# DESIGN7ES.net
KiCad netlist of a schematic drawn in EAGLE
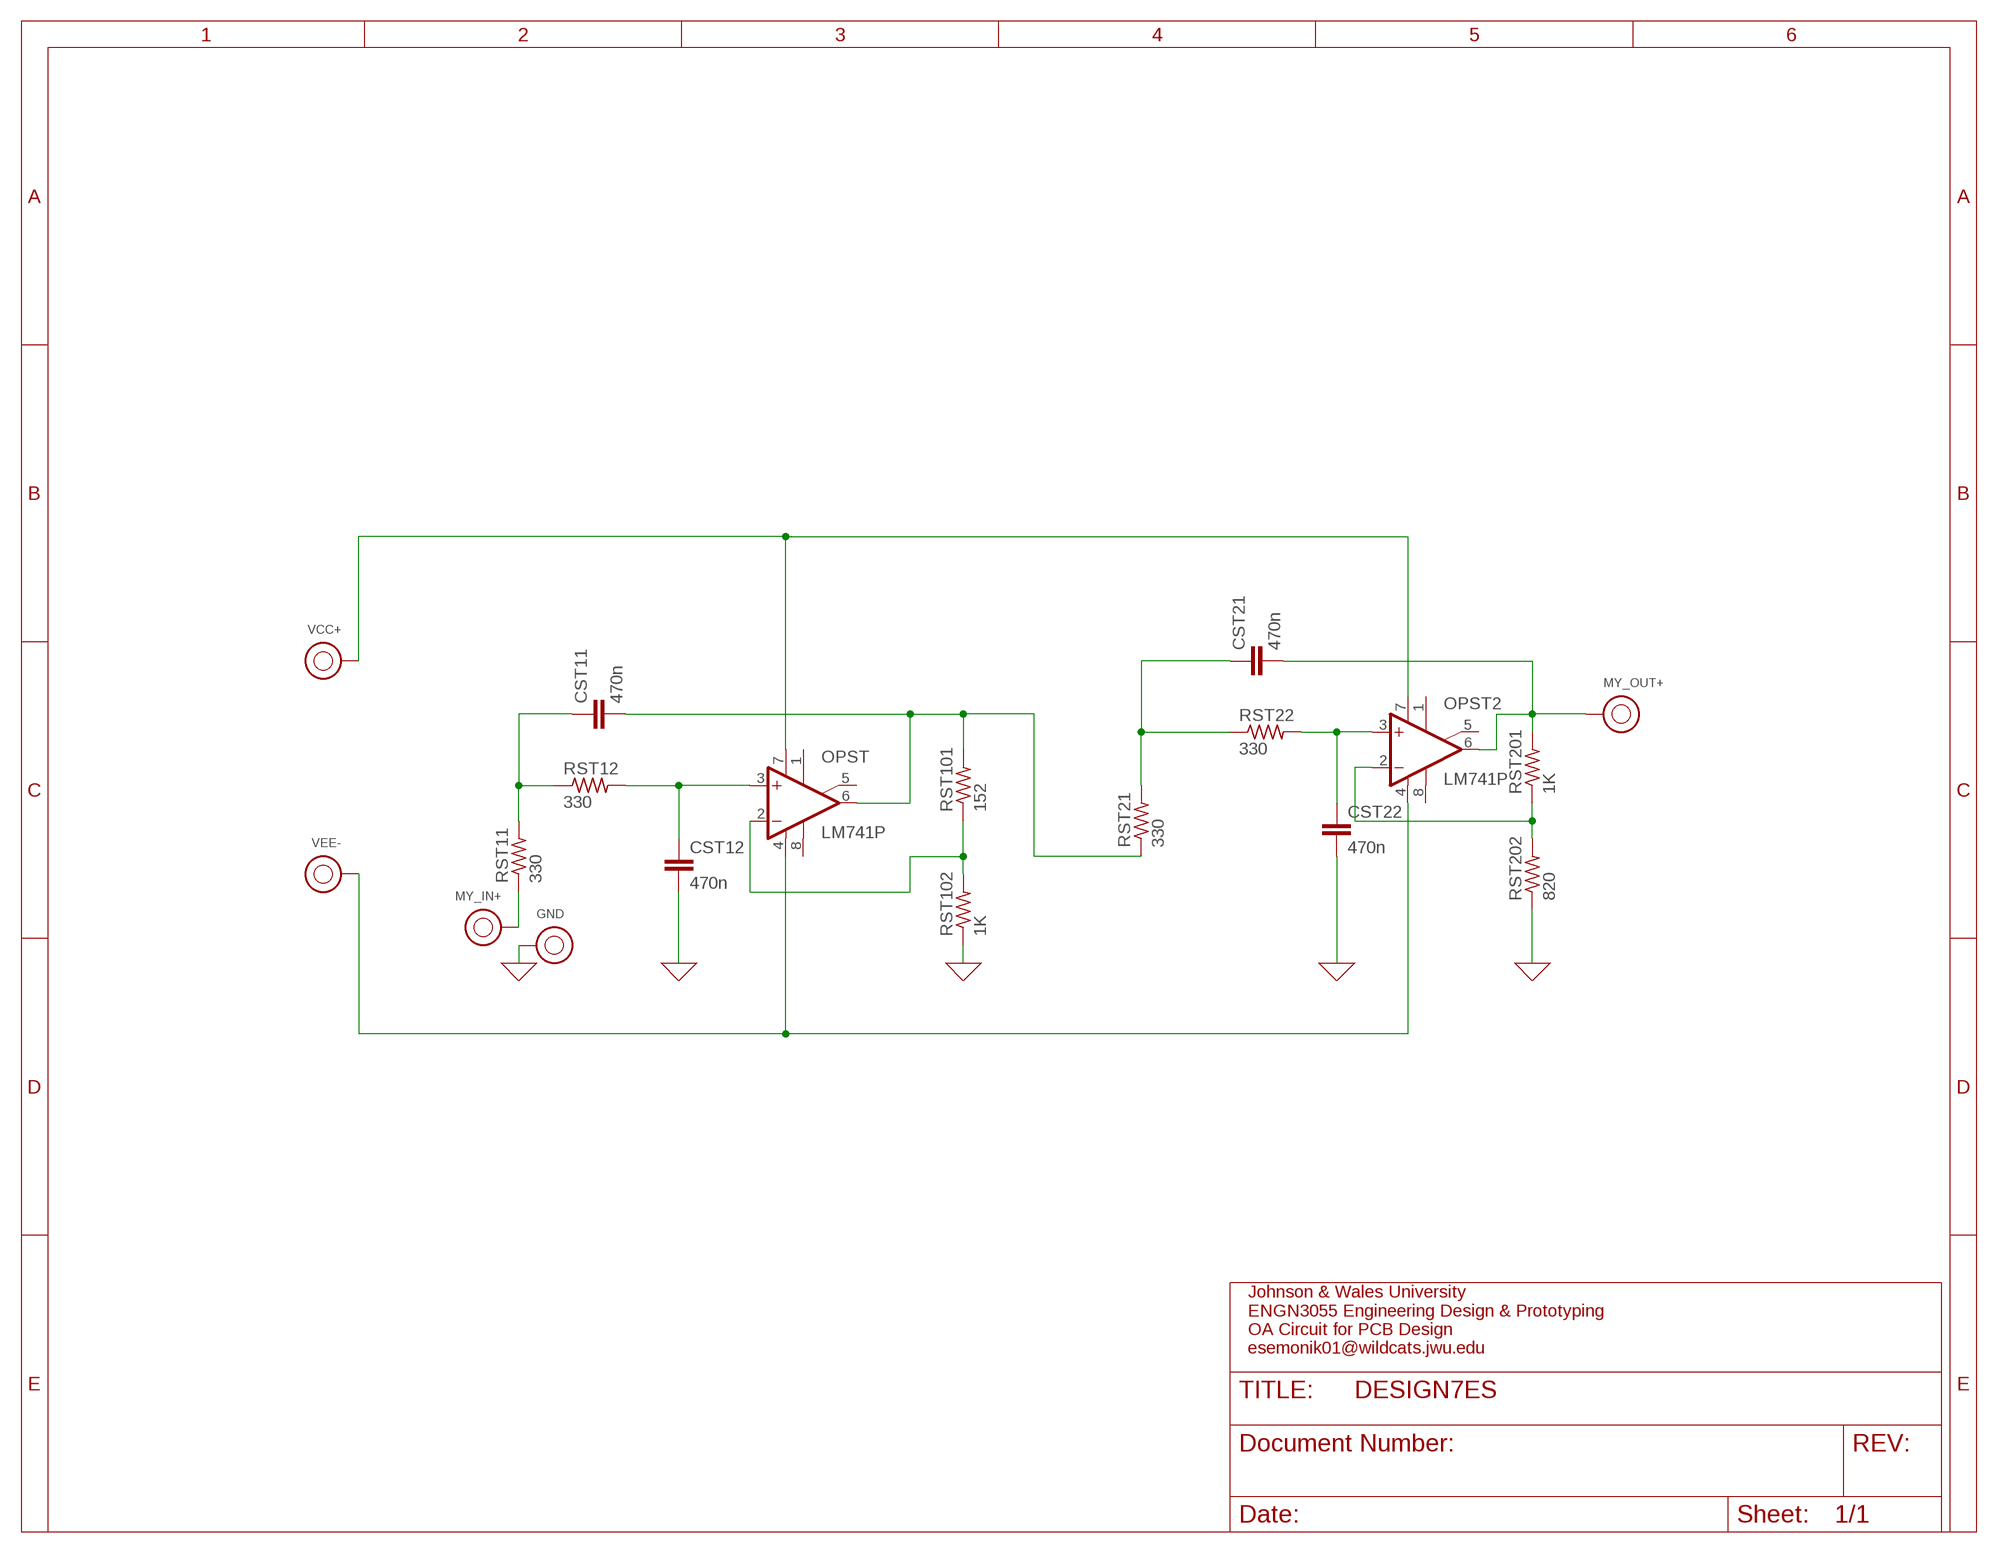
[diagram p0: schematic, sheet 1]

(export (version "E")
  (design (tool "Eeschema 10.0.6"))
  (components
    (comp (ref "CST11")
      (value "470n")
      (footprint "eagle-import:C2.5-2")
      (libsource (lib "eagle-import") (part "C2.5/2"))
    )
    (comp (ref "CST12")
      (value "470n")
      (footprint "eagle-import:C2.5-2")
      (libsource (lib "eagle-import") (part "C2.5/2"))
    )
    (comp (ref "CST21")
      (value "470n")
      (footprint "eagle-import:C2.5-2")
      (libsource (lib "eagle-import") (part "C2.5/2"))
    )
    (comp (ref "CST22")
      (value "470n")
      (footprint "eagle-import:C2.5-2")
      (libsource (lib "eagle-import") (part "C2.5/2"))
    )
    (comp (ref "GND")
      (value "BINDING-POST")
      (footprint "eagle-import:BINDING-POST")
      (libsource (lib "eagle-import") (part "BINDING-POST"))
    )
    (comp (ref "MY_IN+")
      (value "BINDING-POST")
      (footprint "eagle-import:BINDING-POST")
      (libsource (lib "eagle-import") (part "BINDING-POST"))
    )
    (comp (ref "MY_OUT+")
      (value "BINDING-POST")
      (footprint "eagle-import:BINDING-POST")
      (libsource (lib "eagle-import") (part "BINDING-POST"))
    )
    (comp (ref "OPST")
      (value "LM741P")
      (footprint "eagle-import:DIL08")
      (libsource (lib "eagle-import") (part "741PLM"))
    )
    (comp (ref "OPST2")
      (value "LM741P")
      (footprint "eagle-import:DIL08")
      (libsource (lib "eagle-import") (part "741PLM"))
    )
    (comp (ref "RST11")
      (value "330")
      (footprint "eagle-import:0204_5")
      (libsource (lib "eagle-import") (part "R-US_0204/5"))
    )
    (comp (ref "RST12")
      (value "330")
      (footprint "eagle-import:0204_5")
      (libsource (lib "eagle-import") (part "R-US_0204/5"))
    )
    (comp (ref "RST21")
      (value "330")
      (footprint "eagle-import:0204_5")
      (libsource (lib "eagle-import") (part "R-US_0204/5"))
    )
    (comp (ref "RST22")
      (value "330")
      (footprint "eagle-import:0204_5")
      (libsource (lib "eagle-import") (part "R-US_0204/5"))
    )
    (comp (ref "RST101")
      (value "152")
      (footprint "eagle-import:0204_5")
      (libsource (lib "eagle-import") (part "R-US_0204/5"))
    )
    (comp (ref "RST102")
      (value "1K")
      (footprint "eagle-import:0204_5")
      (libsource (lib "eagle-import") (part "R-US_0204/5"))
    )
    (comp (ref "RST201")
      (value "1K")
      (footprint "eagle-import:0204_5")
      (libsource (lib "eagle-import") (part "R-US_0204/5"))
    )
    (comp (ref "RST202")
      (value "820")
      (footprint "eagle-import:0204_5")
      (libsource (lib "eagle-import") (part "R-US_0204/5"))
    )
    (comp (ref "VCC+")
      (value "BINDING-POST")
      (footprint "eagle-import:BINDING-POST")
      (libsource (lib "eagle-import") (part "BINDING-POST"))
    )
    (comp (ref "VEE-")
      (value "BINDING-POST")
      (footprint "eagle-import:BINDING-POST")
      (libsource (lib "eagle-import") (part "BINDING-POST"))
    )
  )
  (nets
    (net (code "1") (name "GND") (class "Default")
      (node (ref "CST12") (pin "2") (pinfunction "2_2") (pintype "passive"))
      (node (ref "CST22") (pin "2") (pinfunction "2_2") (pintype "passive"))
      (node (ref "GND") (pin "1") (pinfunction "1_1") (pintype "passive"))
      (node (ref "GND") (pin "1_1") (pinfunction "1_1_1") (pintype "passive"))
      (node (ref "GND") (pin "1_2") (pinfunction "1_1_2") (pintype "passive"))
      (node (ref "GND") (pin "1_3") (pinfunction "1_1_3") (pintype "passive"))
      (node (ref "GND") (pin "1_4") (pinfunction "1_1_4") (pintype "passive"))
      (node (ref "GND") (pin "1_5") (pinfunction "1_1_5") (pintype "passive"))
      (node (ref "GND") (pin "1_6") (pinfunction "1_1_6") (pintype "passive"))
      (node (ref "GND") (pin "1_7") (pinfunction "1_1_7") (pintype "passive"))
      (node (ref "GND") (pin "1_8") (pinfunction "1_1_8") (pintype "passive"))
      (node (ref "RST102") (pin "1") (pinfunction "1_1") (pintype "passive"))
      (node (ref "RST202") (pin "1") (pinfunction "1_1") (pintype "passive"))
    )
    (net (code "2") (name "Net-(CST11-Pad1)") (class "Default")
      (node (ref "CST11") (pin "1") (pinfunction "1_1") (pintype "passive"))
      (node (ref "RST11") (pin "2") (pinfunction "2_2") (pintype "passive"))
      (node (ref "RST12") (pin "1") (pinfunction "1_1") (pintype "passive"))
    )
    (net (code "3") (name "Net-(CST21-Pad1)") (class "Default")
      (node (ref "CST21") (pin "1") (pinfunction "1_1") (pintype "passive"))
      (node (ref "RST21") (pin "2") (pinfunction "2_2") (pintype "passive"))
      (node (ref "RST22") (pin "1") (pinfunction "1_1") (pintype "passive"))
    )
    (net (code "4") (name "Net-(MY_IN+-1-Pad1_1)") (class "Default")
      (node (ref "MY_IN+") (pin "1") (pinfunction "1_1") (pintype "passive"))
      (node (ref "MY_IN+") (pin "1_1") (pinfunction "1_1_1") (pintype "passive"))
      (node (ref "MY_IN+") (pin "1_2") (pinfunction "1_1_2") (pintype "passive"))
      (node (ref "MY_IN+") (pin "1_3") (pinfunction "1_1_3") (pintype "passive"))
      (node (ref "MY_IN+") (pin "1_4") (pinfunction "1_1_4") (pintype "passive"))
      (node (ref "MY_IN+") (pin "1_5") (pinfunction "1_1_5") (pintype "passive"))
      (node (ref "MY_IN+") (pin "1_6") (pinfunction "1_1_6") (pintype "passive"))
      (node (ref "MY_IN+") (pin "1_7") (pinfunction "1_1_7") (pintype "passive"))
      (node (ref "MY_IN+") (pin "1_8") (pinfunction "1_1_8") (pintype "passive"))
      (node (ref "RST11") (pin "1") (pinfunction "1_1") (pintype "passive"))
    )
    (net (code "5") (name "Net-(OPST-+IN)") (class "Default")
      (node (ref "CST12") (pin "1") (pinfunction "1_1") (pintype "passive"))
      (node (ref "OPST") (pin "3") (pinfunction "+IN_3") (pintype "input"))
      (node (ref "RST12") (pin "2") (pinfunction "2_2") (pintype "passive"))
    )
    (net (code "6") (name "Net-(OPST--IN)") (class "Default")
      (node (ref "OPST") (pin "2") (pinfunction "-IN_2") (pintype "input"))
      (node (ref "RST101") (pin "1") (pinfunction "1_1") (pintype "passive"))
      (node (ref "RST102") (pin "2") (pinfunction "2_2") (pintype "passive"))
    )
    (net (code "7") (name "Net-(OPST-OUT)") (class "Default")
      (node (ref "CST11") (pin "2") (pinfunction "2_2") (pintype "passive"))
      (node (ref "OPST") (pin "6") (pinfunction "OUT_6") (pintype "output"))
      (node (ref "RST101") (pin "2") (pinfunction "2_2") (pintype "passive"))
      (node (ref "RST21") (pin "1") (pinfunction "1_1") (pintype "passive"))
    )
    (net (code "8") (name "Net-(OPST-V+)") (class "Default")
      (node (ref "OPST") (pin "7") (pinfunction "V+_7") (pintype "power_in"))
      (node (ref "OPST2") (pin "7") (pinfunction "V+_7") (pintype "power_in"))
      (node (ref "VCC+") (pin "1") (pinfunction "1_1") (pintype "passive"))
      (node (ref "VCC+") (pin "1_1") (pinfunction "1_1_1") (pintype "passive"))
      (node (ref "VCC+") (pin "1_2") (pinfunction "1_1_2") (pintype "passive"))
      (node (ref "VCC+") (pin "1_3") (pinfunction "1_1_3") (pintype "passive"))
      (node (ref "VCC+") (pin "1_4") (pinfunction "1_1_4") (pintype "passive"))
      (node (ref "VCC+") (pin "1_5") (pinfunction "1_1_5") (pintype "passive"))
      (node (ref "VCC+") (pin "1_6") (pinfunction "1_1_6") (pintype "passive"))
      (node (ref "VCC+") (pin "1_7") (pinfunction "1_1_7") (pintype "passive"))
      (node (ref "VCC+") (pin "1_8") (pinfunction "1_1_8") (pintype "passive"))
    )
    (net (code "9") (name "Net-(OPST-V-)") (class "Default")
      (node (ref "OPST") (pin "4") (pinfunction "V-_4") (pintype "power_in"))
      (node (ref "OPST2") (pin "4") (pinfunction "V-_4") (pintype "power_in"))
      (node (ref "VEE-") (pin "1") (pinfunction "1_1") (pintype "passive"))
      (node (ref "VEE-") (pin "1_1") (pinfunction "1_1_1") (pintype "passive"))
      (node (ref "VEE-") (pin "1_2") (pinfunction "1_1_2") (pintype "passive"))
      (node (ref "VEE-") (pin "1_3") (pinfunction "1_1_3") (pintype "passive"))
      (node (ref "VEE-") (pin "1_4") (pinfunction "1_1_4") (pintype "passive"))
      (node (ref "VEE-") (pin "1_5") (pinfunction "1_1_5") (pintype "passive"))
      (node (ref "VEE-") (pin "1_6") (pinfunction "1_1_6") (pintype "passive"))
      (node (ref "VEE-") (pin "1_7") (pinfunction "1_1_7") (pintype "passive"))
      (node (ref "VEE-") (pin "1_8") (pinfunction "1_1_8") (pintype "passive"))
    )
    (net (code "10") (name "Net-(OPST2-+IN)") (class "Default")
      (node (ref "CST22") (pin "1") (pinfunction "1_1") (pintype "passive"))
      (node (ref "OPST2") (pin "3") (pinfunction "+IN_3") (pintype "input"))
      (node (ref "RST22") (pin "2") (pinfunction "2_2") (pintype "passive"))
    )
    (net (code "11") (name "Net-(OPST2--IN)") (class "Default")
      (node (ref "OPST2") (pin "2") (pinfunction "-IN_2") (pintype "input"))
      (node (ref "RST201") (pin "1") (pinfunction "1_1") (pintype "passive"))
      (node (ref "RST202") (pin "2") (pinfunction "2_2") (pintype "passive"))
    )
    (net (code "12") (name "Net-(OPST2-OUT)") (class "Default")
      (node (ref "CST21") (pin "2") (pinfunction "2_2") (pintype "passive"))
      (node (ref "MY_OUT+") (pin "1") (pinfunction "1_1") (pintype "passive"))
      (node (ref "MY_OUT+") (pin "1_1") (pinfunction "1_1_1") (pintype "passive"))
      (node (ref "MY_OUT+") (pin "1_2") (pinfunction "1_1_2") (pintype "passive"))
      (node (ref "MY_OUT+") (pin "1_3") (pinfunction "1_1_3") (pintype "passive"))
      (node (ref "MY_OUT+") (pin "1_4") (pinfunction "1_1_4") (pintype "passive"))
      (node (ref "MY_OUT+") (pin "1_5") (pinfunction "1_1_5") (pintype "passive"))
      (node (ref "MY_OUT+") (pin "1_6") (pinfunction "1_1_6") (pintype "passive"))
      (node (ref "MY_OUT+") (pin "1_7") (pinfunction "1_1_7") (pintype "passive"))
      (node (ref "MY_OUT+") (pin "1_8") (pinfunction "1_1_8") (pintype "passive"))
      (node (ref "OPST2") (pin "6") (pinfunction "OUT_6") (pintype "output"))
      (node (ref "RST201") (pin "2") (pinfunction "2_2") (pintype "passive"))
    )
    (net (code "13") (name "unconnected-(OPST-ON1-Pad1)") (class "Default")
      (node (ref "OPST") (pin "1") (pinfunction "ON1_1") (pintype "passive"))
    )
    (net (code "14") (name "unconnected-(OPST-ON2-Pad5)") (class "Default")
      (node (ref "OPST") (pin "5") (pinfunction "ON2_5") (pintype "passive"))
    )
    (net (code "15") (name "unconnected-(OPST-OPT-Pad8)") (class "Default")
      (node (ref "OPST") (pin "8") (pinfunction "OPT_8") (pintype "passive"))
    )
    (net (code "16") (name "unconnected-(OPST2-ON1-Pad1)") (class "Default")
      (node (ref "OPST2") (pin "1") (pinfunction "ON1_1") (pintype "passive"))
    )
    (net (code "17") (name "unconnected-(OPST2-ON2-Pad5)") (class "Default")
      (node (ref "OPST2") (pin "5") (pinfunction "ON2_5") (pintype "passive"))
    )
    (net (code "18") (name "unconnected-(OPST2-OPT-Pad8)") (class "Default")
      (node (ref "OPST2") (pin "8") (pinfunction "OPT_8") (pintype "passive"))
    )
  )
)
